# TeamFlag.net
KiCad netlist of a schematic drawn in EAGLE
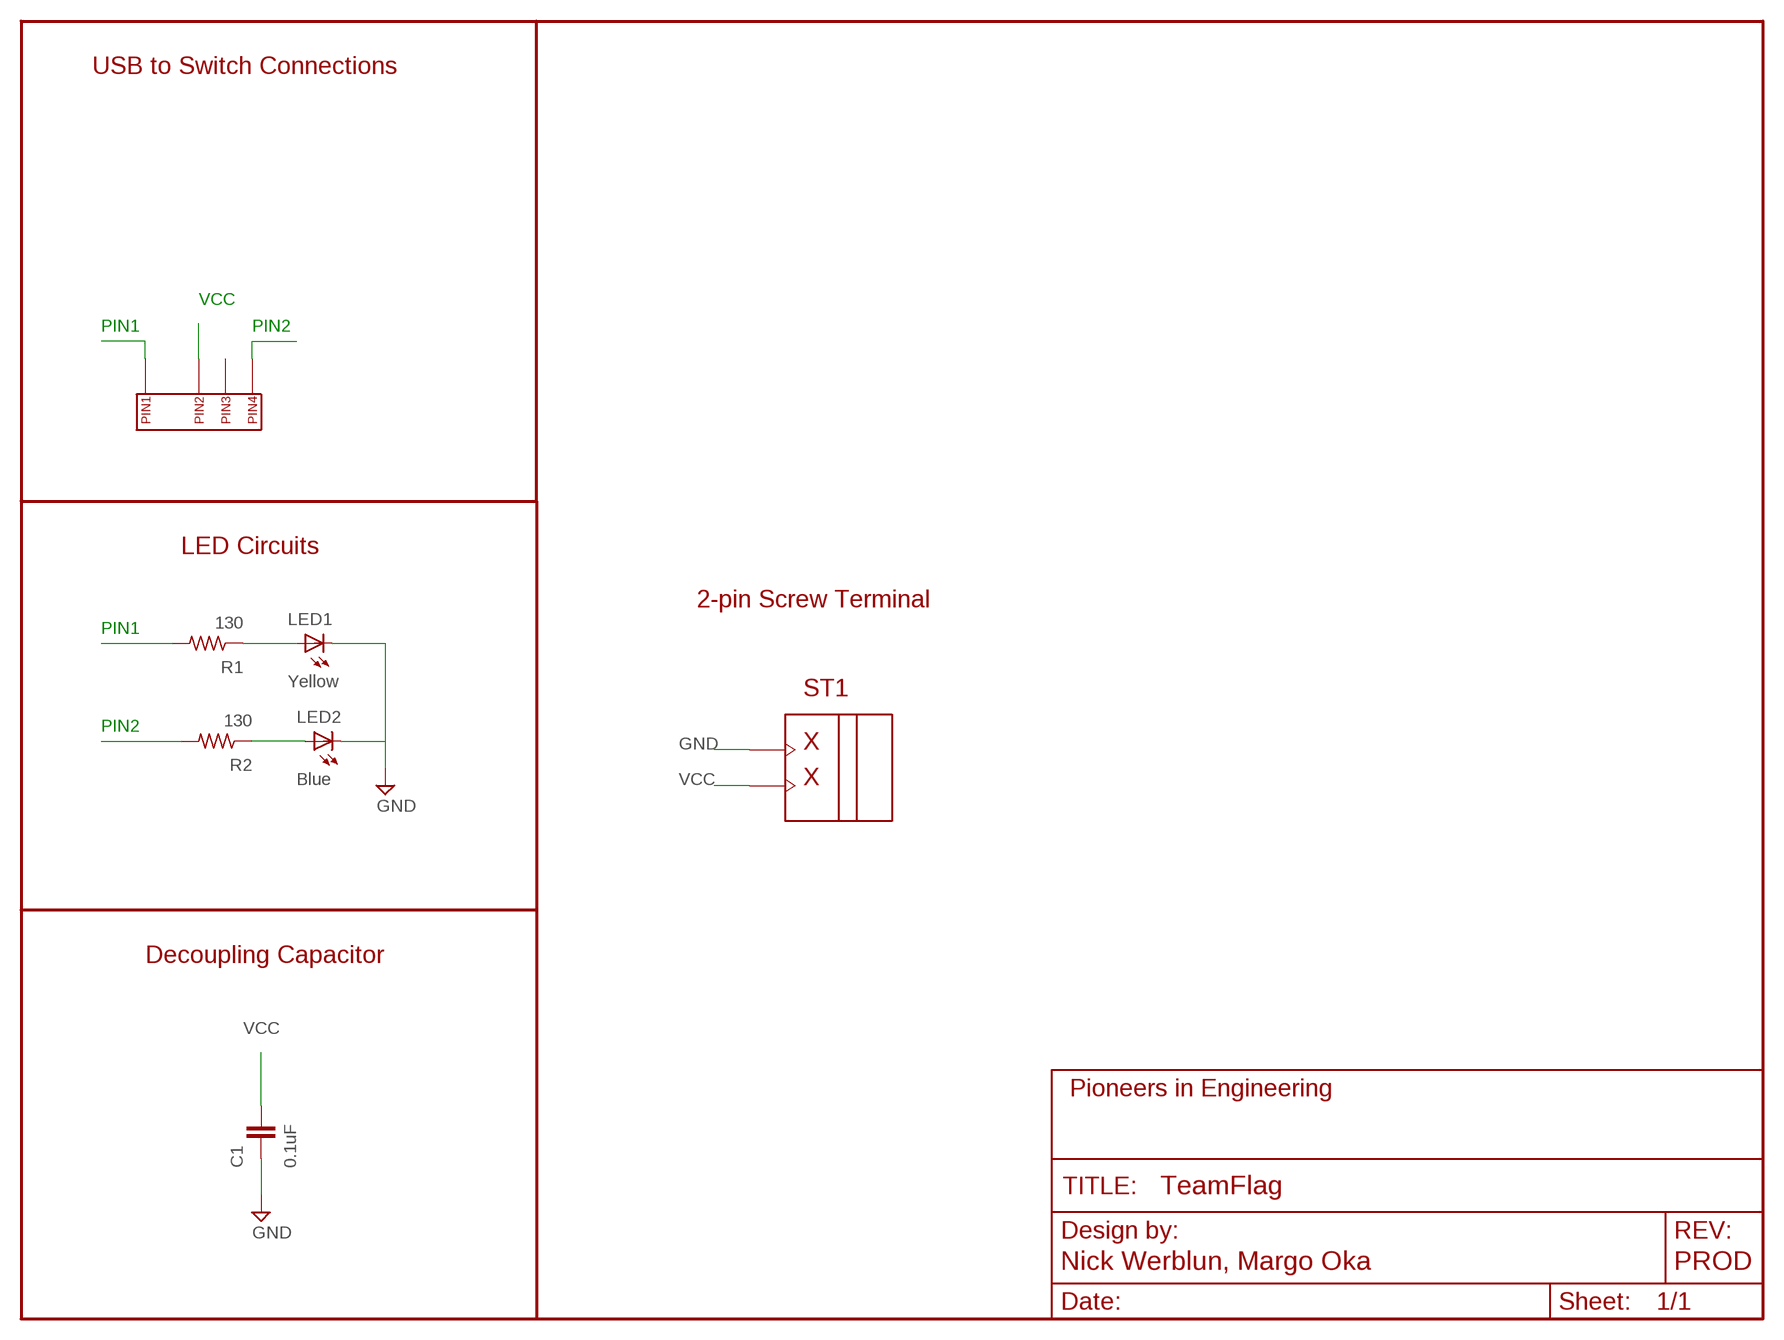
[diagram p0: schematic, sheet 1]

(export (version "E")
  (design (tool "Eeschema 10.0.6"))
  (components
    (comp (ref "C1")
      (value "0.1uF")
      (footprint "eagle-import:0603-CAP")
      (libsource (lib "eagle-import") (part "CAP0603-CAP"))
    )
    (comp (ref "LED1")
      (value "Yellow")
      (footprint "eagle-import:LED5MM-NOFLAT")
      (libsource (lib "eagle-import") (part "LEDLED5MM-NOFLAT"))
    )
    (comp (ref "LED2")
      (value "Blue")
      (footprint "eagle-import:LED5MM-NOFLAT")
      (libsource (lib "eagle-import") (part "LEDLED5MM-NOFLAT"))
    )
    (comp (ref "R1")
      (value "130")
      (footprint "eagle-import:R0603")
      (fields (field (name "MANUFACTURER") "Rohm Semiconductor"))
      (libsource (lib "eagle-import") (part "R-US_R0603"))
    )
    (comp (ref "R2")
      (value "130")
      (footprint "eagle-import:R0603")
      (fields (field (name "MANUFACTURER") "Rohm Semiconductor"))
      (libsource (lib "eagle-import") (part "R-US_R0603"))
    )
    (comp (ref "ST1")
      (value "2PIN_SCREW")
      (footprint "eagle-import:2PIN_SCREW")
      (libsource (lib "eagle-import") (part "2PIN_SCREW"))
    )
    (comp (ref "U$2")
      (value "SP3T_SLIDE_SWITCH")
      (footprint "eagle-import:SP3T_SLIDE_SWITCH")
      (libsource (lib "eagle-import") (part "SP3T_SLIDE_SWITCH"))
    )
  )
  (nets
    (net (code "1") (name "/PIN1") (class "Default")
      (node (ref "R1") (pin "2") (pinfunction "2_2") (pintype "passive"))
      (node (ref "U$2") (pin "PIN1") (pinfunction "PIN1_PIN1") (pintype "bidirectional"))
    )
    (net (code "2") (name "/PIN4") (class "Default")
      (node (ref "R2") (pin "2") (pinfunction "2_2") (pintype "passive"))
      (node (ref "U$2") (pin "PIN4") (pinfunction "PIN4_PIN4") (pintype "bidirectional"))
    )
    (net (code "3") (name "/VCC") (class "Default")
      (node (ref "C1") (pin "2") (pinfunction "2_2") (pintype "passive"))
      (node (ref "ST1") (pin "P$2") (pinfunction "P$2_P$2") (pintype "bidirectional"))
      (node (ref "U$2") (pin "PIN2") (pinfunction "PIN2_PIN2") (pintype "bidirectional"))
    )
    (net (code "4") (name "GND") (class "Default")
      (node (ref "C1") (pin "1") (pinfunction "1_1") (pintype "passive"))
      (node (ref "LED1") (pin "K") (pinfunction "C_K") (pintype "passive"))
      (node (ref "LED2") (pin "K") (pinfunction "C_K") (pintype "passive"))
      (node (ref "ST1") (pin "P$1") (pinfunction "P$1_P$1") (pintype "bidirectional"))
    )
    (net (code "5") (name "Net-(LED1-PadA)") (class "Default")
      (node (ref "LED1") (pin "A") (pinfunction "A_A") (pintype "passive"))
      (node (ref "R1") (pin "1") (pinfunction "1_1") (pintype "passive"))
    )
    (net (code "6") (name "Net-(LED2-PadA)") (class "Default")
      (node (ref "LED2") (pin "A") (pinfunction "A_A") (pintype "passive"))
      (node (ref "R2") (pin "1") (pinfunction "1_1") (pintype "passive"))
    )
    (net (code "7") (name "unconnected-(U$2-PadPIN3)") (class "Default")
      (node (ref "U$2") (pin "PIN3") (pinfunction "PIN3_PIN3") (pintype "bidirectional"))
    )
  )
)
